# Main.net
KiCad netlist of a schematic drawn in Altium Designer
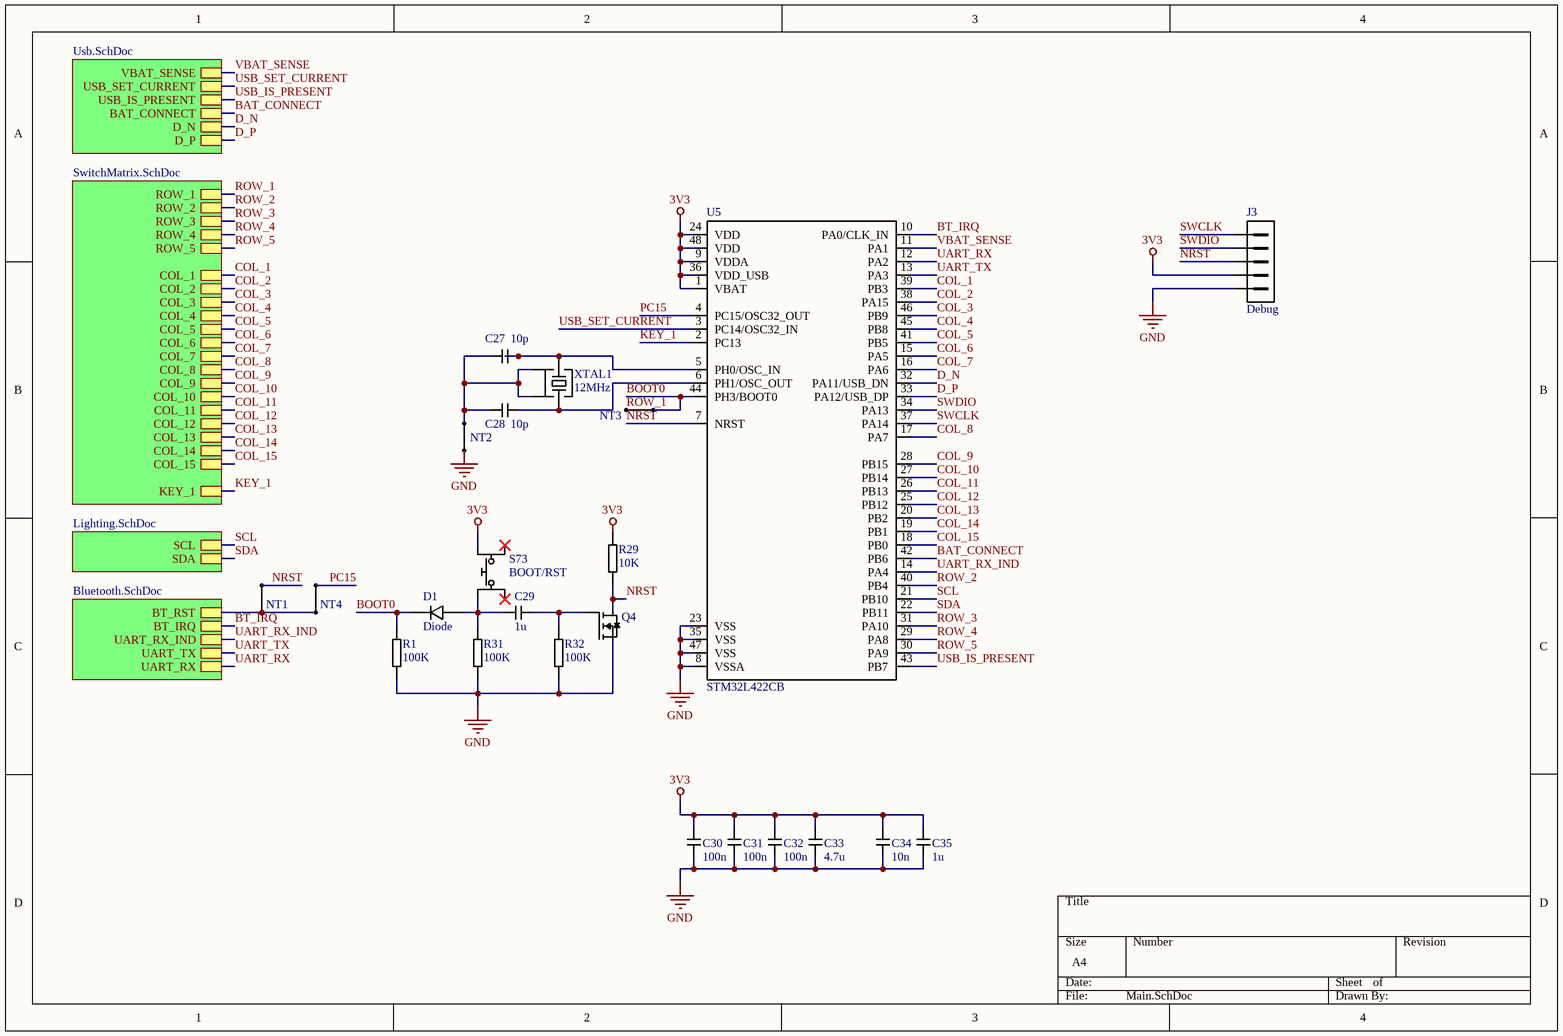
[diagram p0: Main.SchDoc]

(export (version "E")
  (design (tool "Eeschema 10.0.6"))
  (components
    (comp (ref "C27")
      (value "10p")
      (footprint "Capacitor_0603")
      (libsource (lib "NautilusKB") (part "Capacitor"))
    )
    (comp (ref "C28")
      (value "10p")
      (footprint "Capacitor_0603")
      (libsource (lib "NautilusKB") (part "Capacitor"))
    )
    (comp (ref "C29")
      (value "1u")
      (footprint "Capacitor_0603")
      (libsource (lib "NautilusKB") (part "Capacitor"))
    )
    (comp (ref "C30")
      (value "100n")
      (footprint "Capacitor_0603")
      (libsource (lib "NautilusKB") (part "Capacitor"))
    )
    (comp (ref "C31")
      (value "100n")
      (footprint "Capacitor_0603")
      (libsource (lib "NautilusKB") (part "Capacitor"))
    )
    (comp (ref "C32")
      (value "100n")
      (footprint "Capacitor_0603")
      (libsource (lib "NautilusKB") (part "Capacitor"))
    )
    (comp (ref "C33")
      (value "4.7u")
      (footprint "Capacitor_0603")
      (libsource (lib "NautilusKB") (part "Capacitor"))
    )
    (comp (ref "C34")
      (value "10n")
      (footprint "Capacitor_0603")
      (libsource (lib "NautilusKB") (part "Capacitor"))
    )
    (comp (ref "C35")
      (value "1u")
      (footprint "Capacitor_0603")
      (libsource (lib "NautilusKB") (part "Capacitor"))
    )
    (comp (ref "D1") (value "Diode") (footprint "SOD_323") (libsource (lib "NautilusKB") (part "Diode")))
    (comp (ref "J3")
      (value "Debug")
      (footprint "Header_male_1x5_1.27mm")
      (libsource (lib "NautilusKB") (part "Connector_5P"))
    )
    (comp (ref "NT1")
      (value "Net tie")
      (footprint "Resistor_0603")
      (libsource (lib "NautilusKB") (part "Net tie"))
    )
    (comp (ref "NT2") (value "Net tie") (footprint "Net_tie") (libsource (lib "NautilusKB") (part "Net tie")))
    (comp (ref "NT3") (value "Net tie") (footprint "Net_tie") (libsource (lib "NautilusKB") (part "Net tie")))
    (comp (ref "NT4")
      (value "Net tie")
      (footprint "Resistor_0603")
      (libsource (lib "NautilusKB") (part "Net tie"))
    )
    (comp (ref "Q4") (value "NMOS") (footprint "SOT_233") (libsource (lib "NautilusKB") (part "NMOS")))
    (comp (ref "R1")
      (value "100K")
      (footprint "Resistor_0603")
      (libsource (lib "NautilusKB") (part "Resistor"))
    )
    (comp (ref "R29")
      (value "10K")
      (footprint "Resistor_0603")
      (libsource (lib "NautilusKB") (part "Resistor"))
    )
    (comp (ref "R31")
      (value "100K")
      (footprint "Resistor_0603")
      (libsource (lib "NautilusKB") (part "Resistor"))
    )
    (comp (ref "R32")
      (value "100K")
      (footprint "Resistor_0603")
      (libsource (lib "NautilusKB") (part "Resistor"))
    )
    (comp (ref "S73")
      (value "BOOT/RST")
      (footprint "Tactile_switch_3.5x3mm_4P")
      (libsource (lib "NautilusKB") (part "Pushbutton_4P"))
    )
    (comp (ref "U5")
      (value "STM32L422CB")
      (footprint "QFP_48_7mm")
      (libsource (lib "NautilusKB") (part "STM32L422CB"))
    )
    (comp (ref "XTAL1")
      (value "12MHz")
      (footprint "Crystal_3225")
      (libsource (lib "NautilusKB") (part "Crystal_4P"))
    )
  )
  (nets
    (net (code "1") (name "/BAT_CONNECT") (class "Default")
      (node (ref "U5") (pin "42") (pinfunction "PB6_42") (pintype "passive"))
    )
    (net (code "2") (name "/BOOT0") (class "Default")
      (node (ref "D1") (pin "K") (pintype "passive"))
      (node (ref "NT3") (pin "2") (pintype "passive"))
      (node (ref "R1") (pin "2") (pintype "passive"))
      (node (ref "U5") (pin "44") (pinfunction "PH3/BOOT0_44") (pintype "passive"))
    )
    (net (code "3") (name "/BT_IRQ") (class "Default")
      (node (ref "U5") (pin "10") (pinfunction "PA0/CLK_IN_10") (pintype "passive"))
    )
    (net (code "4") (name "/BT_RST") (class "Default")
      (node (ref "NT1") (pin "1") (pintype "passive"))
      (node (ref "NT4") (pin "1") (pintype "passive"))
    )
    (net (code "5") (name "/COL_1") (class "Default")
      (node (ref "U5") (pin "39") (pinfunction "PB3_39") (pintype "passive"))
    )
    (net (code "6") (name "/COL_2") (class "Default")
      (node (ref "U5") (pin "38") (pinfunction "PA15_38") (pintype "passive"))
    )
    (net (code "7") (name "/COL_3") (class "Default")
      (node (ref "U5") (pin "46") (pinfunction "PB9_46") (pintype "passive"))
    )
    (net (code "8") (name "/COL_4") (class "Default")
      (node (ref "U5") (pin "45") (pinfunction "PB8_45") (pintype "passive"))
    )
    (net (code "9") (name "/COL_5") (class "Default")
      (node (ref "U5") (pin "41") (pinfunction "PB5_41") (pintype "passive"))
    )
    (net (code "10") (name "/COL_6") (class "Default")
      (node (ref "U5") (pin "15") (pinfunction "PA5_15") (pintype "passive"))
    )
    (net (code "11") (name "/COL_7") (class "Default")
      (node (ref "U5") (pin "16") (pinfunction "PA6_16") (pintype "passive"))
    )
    (net (code "12") (name "/COL_8") (class "Default")
      (node (ref "U5") (pin "17") (pinfunction "PA7_17") (pintype "passive"))
    )
    (net (code "13") (name "/COL_9") (class "Default")
      (node (ref "U5") (pin "28") (pinfunction "PB15_28") (pintype "passive"))
    )
    (net (code "14") (name "/COL_10") (class "Default")
      (node (ref "U5") (pin "27") (pinfunction "PB14_27") (pintype "passive"))
    )
    (net (code "15") (name "/COL_11") (class "Default")
      (node (ref "U5") (pin "26") (pinfunction "PB13_26") (pintype "passive"))
    )
    (net (code "16") (name "/COL_12") (class "Default")
      (node (ref "U5") (pin "25") (pinfunction "PB12_25") (pintype "passive"))
    )
    (net (code "17") (name "/COL_13") (class "Default")
      (node (ref "U5") (pin "20") (pinfunction "PB2_20") (pintype "passive"))
    )
    (net (code "18") (name "/COL_14") (class "Default")
      (node (ref "U5") (pin "19") (pinfunction "PB1_19") (pintype "passive"))
    )
    (net (code "19") (name "/COL_15") (class "Default")
      (node (ref "U5") (pin "18") (pinfunction "PB0_18") (pintype "passive"))
    )
    (net (code "20") (name "/D_N") (class "Default")
      (node (ref "U5") (pin "32") (pinfunction "PA11/USB_DN_32") (pintype "passive"))
    )
    (net (code "21") (name "/D_P") (class "Default")
      (node (ref "U5") (pin "33") (pinfunction "PA12/USB_DP_33") (pintype "passive"))
    )
    (net (code "22") (name "/KEY_1") (class "Default")
      (node (ref "U5") (pin "2") (pinfunction "PC13_2") (pintype "passive"))
    )
    (net (code "23") (name "/NRST") (class "Default")
      (node (ref "J3") (pin "3") (pintype "passive"))
      (node (ref "NT1") (pin "2") (pintype "passive"))
      (node (ref "Q4") (pin "3") (pintype "passive"))
      (node (ref "R29") (pin "1") (pintype "passive"))
      (node (ref "U5") (pin "7") (pinfunction "NRST_7") (pintype "passive"))
    )
    (net (code "24") (name "/PC15") (class "Default")
      (node (ref "NT4") (pin "2") (pintype "passive"))
      (node (ref "U5") (pin "4") (pinfunction "PC15/OSC32_OUT_4") (pintype "passive"))
    )
    (net (code "25") (name "/ROW_1") (class "Default") (node (ref "NT3") (pin "1") (pintype "passive")))
    (net (code "26") (name "/ROW_2") (class "Default")
      (node (ref "U5") (pin "40") (pinfunction "PB4_40") (pintype "passive"))
    )
    (net (code "27") (name "/ROW_3") (class "Default")
      (node (ref "U5") (pin "31") (pinfunction "PA10_31") (pintype "passive"))
    )
    (net (code "28") (name "/ROW_4") (class "Default")
      (node (ref "U5") (pin "29") (pinfunction "PA8_29") (pintype "passive"))
    )
    (net (code "29") (name "/ROW_5") (class "Default")
      (node (ref "U5") (pin "30") (pinfunction "PA9_30") (pintype "passive"))
    )
    (net (code "30") (name "/SCL") (class "Default")
      (node (ref "U5") (pin "21") (pinfunction "PB10_21") (pintype "passive"))
    )
    (net (code "31") (name "/SDA") (class "Default")
      (node (ref "U5") (pin "22") (pinfunction "PB11_22") (pintype "passive"))
    )
    (net (code "32") (name "/SWCLK") (class "Default")
      (node (ref "J3") (pin "2") (pintype "passive"))
      (node (ref "U5") (pin "37") (pinfunction "PA14_37") (pintype "passive"))
    )
    (net (code "33") (name "/SWDIO") (class "Default")
      (node (ref "J3") (pin "1") (pintype "passive"))
      (node (ref "U5") (pin "34") (pinfunction "PA13_34") (pintype "passive"))
    )
    (net (code "34") (name "/UART_RX") (class "Default")
      (node (ref "U5") (pin "12") (pinfunction "PA2_12") (pintype "passive"))
    )
    (net (code "35") (name "/UART_RX_IND") (class "Default")
      (node (ref "U5") (pin "14") (pinfunction "PA4_14") (pintype "passive"))
    )
    (net (code "36") (name "/UART_TX") (class "Default")
      (node (ref "U5") (pin "13") (pinfunction "PA3_13") (pintype "passive"))
    )
    (net (code "37") (name "/USB_IS_PRESENT") (class "Default")
      (node (ref "U5") (pin "43") (pinfunction "PB7_43") (pintype "passive"))
    )
    (net (code "38") (name "/USB_SET_CURRENT") (class "Default")
      (node (ref "U5") (pin "3") (pinfunction "PC14/OSC32_IN_3") (pintype "passive"))
    )
    (net (code "39") (name "/VBAT_SENSE") (class "Default")
      (node (ref "U5") (pin "11") (pinfunction "PA1_11") (pintype "passive"))
    )
    (net (code "40") (name "3V3") (class "Default")
      (node (ref "C30") (pin "2") (pintype "passive"))
      (node (ref "C31") (pin "2") (pintype "passive"))
      (node (ref "C32") (pin "2") (pintype "passive"))
      (node (ref "C33") (pin "2") (pintype "passive"))
      (node (ref "C34") (pin "2") (pintype "passive"))
      (node (ref "C35") (pin "2") (pintype "passive"))
      (node (ref "J3") (pin "4") (pintype "passive"))
      (node (ref "R29") (pin "2") (pintype "passive"))
      (node (ref "S73") (pin "3") (pintype "passive"))
      (node (ref "U5") (pin "1") (pinfunction "VBAT_1") (pintype "passive"))
      (node (ref "U5") (pin "24") (pinfunction "VDD_24") (pintype "passive"))
      (node (ref "U5") (pin "36") (pinfunction "VDD_USB_36") (pintype "passive"))
      (node (ref "U5") (pin "48") (pinfunction "VDD_48") (pintype "passive"))
      (node (ref "U5") (pin "9") (pinfunction "VDDA_9") (pintype "passive"))
    )
    (net (code "41") (name "GND") (class "Default")
      (node (ref "C30") (pin "1") (pintype "passive"))
      (node (ref "C31") (pin "1") (pintype "passive"))
      (node (ref "C32") (pin "1") (pintype "passive"))
      (node (ref "C33") (pin "1") (pintype "passive"))
      (node (ref "C34") (pin "1") (pintype "passive"))
      (node (ref "C35") (pin "1") (pintype "passive"))
      (node (ref "J3") (pin "5") (pintype "passive"))
      (node (ref "NT2") (pin "1") (pintype "passive"))
      (node (ref "Q4") (pin "2") (pintype "passive"))
      (node (ref "R1") (pin "1") (pintype "passive"))
      (node (ref "R31") (pin "1") (pintype "passive"))
      (node (ref "R32") (pin "1") (pintype "passive"))
      (node (ref "U5") (pin "23") (pinfunction "VSS_23") (pintype "passive"))
      (node (ref "U5") (pin "35") (pinfunction "VSS_35") (pintype "passive"))
      (node (ref "U5") (pin "47") (pinfunction "VSS_47") (pintype "passive"))
      (node (ref "U5") (pin "8") (pinfunction "VSSA_8") (pintype "passive"))
    )
    (net (code "42") (name "Net-(C29-Pad1)") (class "Default")
      (node (ref "C29") (pin "1") (pintype "passive"))
      (node (ref "D1") (pin "A") (pintype "passive"))
      (node (ref "R31") (pin "2") (pintype "passive"))
      (node (ref "S73") (pin "1") (pintype "passive"))
    )
    (net (code "43") (name "Net-(C29-Pad2)") (class "Default")
      (node (ref "C29") (pin "2") (pintype "passive"))
      (node (ref "Q4") (pin "1") (pintype "passive"))
      (node (ref "R32") (pin "2") (pintype "passive"))
    )
    (net (code "44") (name "Net-(U5-PH0{slash}OSC_IN)") (class "Default")
      (node (ref "C27") (pin "2") (pintype "passive"))
      (node (ref "U5") (pin "5") (pinfunction "PH0/OSC_IN_5") (pintype "passive"))
      (node (ref "XTAL1") (pin "1") (pintype "passive"))
    )
    (net (code "45") (name "Net-(U5-PH1{slash}OSC_OUT)") (class "Default")
      (node (ref "C28") (pin "2") (pintype "passive"))
      (node (ref "U5") (pin "6") (pinfunction "PH1/OSC_OUT_6") (pintype "passive"))
      (node (ref "XTAL1") (pin "3") (pintype "passive"))
    )
    (net (code "46") (name "Net-(XTAL1-3)") (class "Default")
      (node (ref "C27") (pin "1") (pintype "passive"))
      (node (ref "C28") (pin "1") (pintype "passive"))
      (node (ref "NT2") (pin "2") (pintype "passive"))
      (node (ref "XTAL1") (pin "2") (pinfunction "4_2") (pintype "passive"))
      (node (ref "XTAL1") (pin "4") (pinfunction "3_4") (pintype "passive"))
    )
    (net (code "47") (name "unconnected-(S73-Pad2)") (class "Default")
      (node (ref "S73") (pin "2") (pintype "passive+no_connect"))
    )
    (net (code "48") (name "unconnected-(S73-Pad4)") (class "Default")
      (node (ref "S73") (pin "4") (pintype "passive+no_connect"))
    )
  )
)
